# CR78-GU.net
KiCad netlist of a schematic drawn in EAGLE
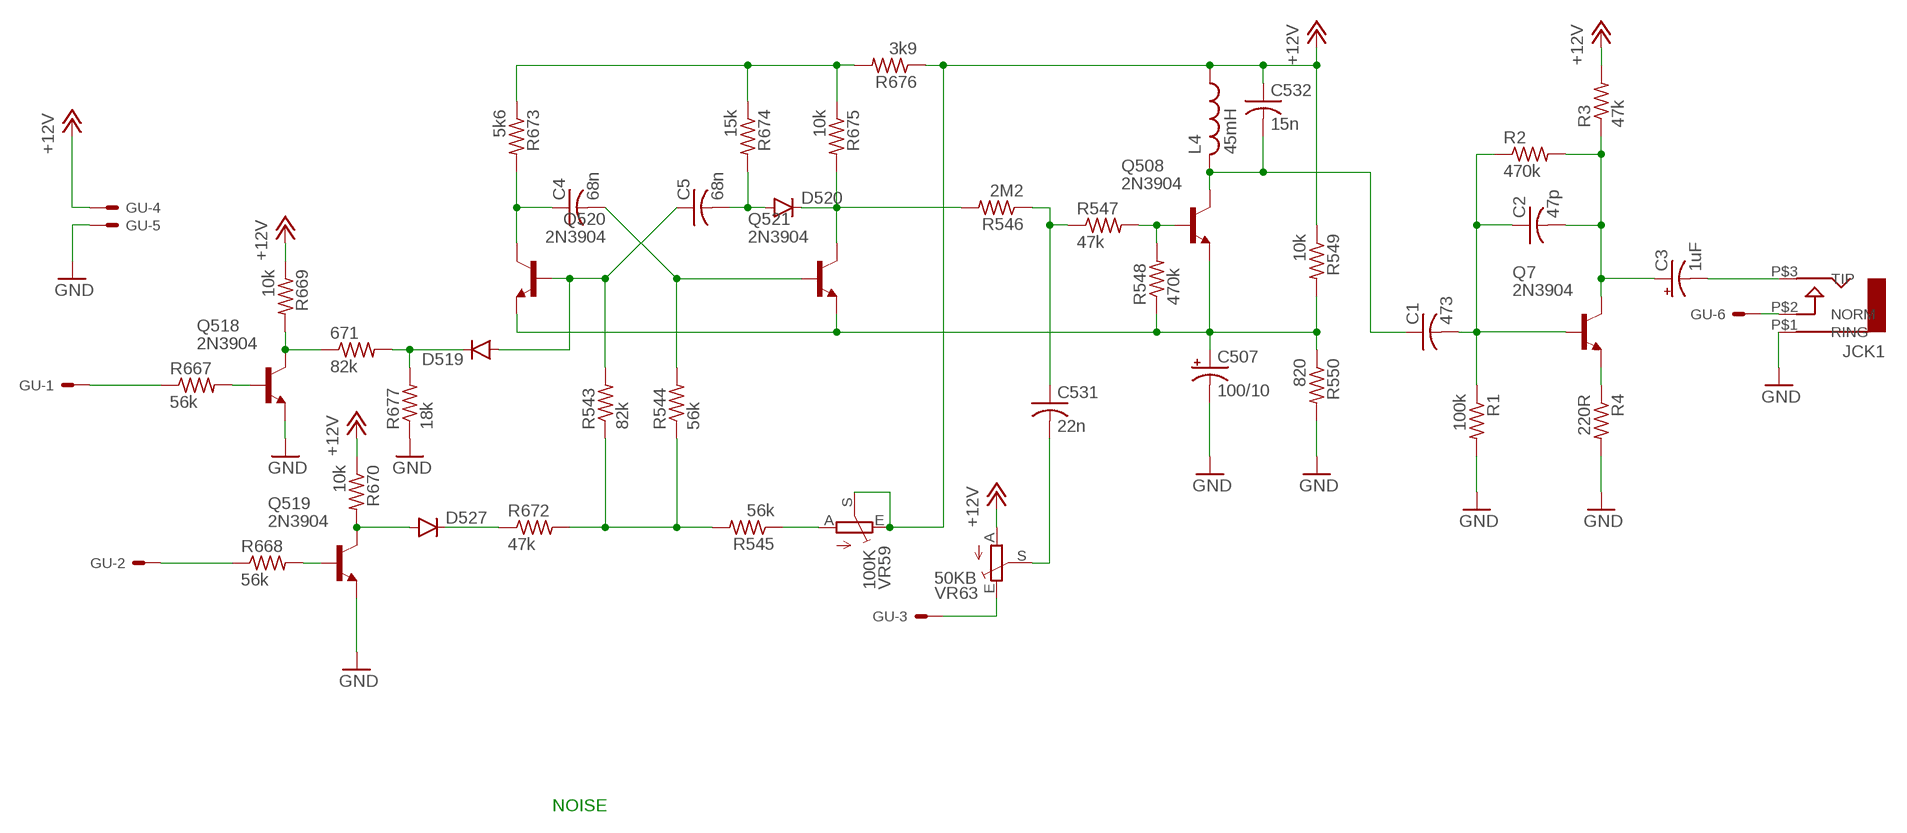
[diagram p0: schematic, sheet 1]

(export (version "E")
  (design (tool "Eeschema 10.0.6"))
  (components
    (comp (ref "671")
      (value "82k")
      (footprint "eagle-import:0207_7")
      (libsource (lib "eagle-import") (part "R-US_0207/7"))
    )
    (comp (ref "C1")
      (value "473")
      (footprint "eagle-import:C050-025X075")
      (libsource (lib "eagle-import") (part "C-US050-025X075"))
    )
    (comp (ref "C2")
      (value "47p")
      (footprint "eagle-import:C050-025X075")
      (libsource (lib "eagle-import") (part "C-US050-025X075"))
    )
    (comp (ref "C3")
      (value "1uF")
      (footprint "eagle-import:B45181A")
      (libsource (lib "eagle-import") (part "CPOL-USB45181A"))
    )
    (comp (ref "C4")
      (value "68n")
      (footprint "eagle-import:C050-025X075")
      (libsource (lib "eagle-import") (part "C-US050-025X075"))
    )
    (comp (ref "C5")
      (value "68n")
      (footprint "eagle-import:C050-025X075")
      (libsource (lib "eagle-import") (part "C-US050-025X075"))
    )
    (comp (ref "C507")
      (value "100/10")
      (footprint "eagle-import:B45181A")
      (libsource (lib "eagle-import") (part "CPOL-USB45181A"))
    )
    (comp (ref "C531")
      (value "22n")
      (footprint "eagle-import:C050-025X075")
      (libsource (lib "eagle-import") (part "C-US050-025X075"))
    )
    (comp (ref "C532")
      (value "15n")
      (footprint "eagle-import:C050-025X075")
      (libsource (lib "eagle-import") (part "C-US050-025X075"))
    )
    (comp (ref "D519")
      (value "DIODE1N4148")
      (footprint "eagle-import:DIODE-1N4148")
      (libsource (lib "eagle-import") (part "DIODE1N4148"))
    )
    (comp (ref "D520")
      (value "DIODE1N4148")
      (footprint "eagle-import:DIODE-1N4148")
      (libsource (lib "eagle-import") (part "DIODE1N4148"))
    )
    (comp (ref "D527")
      (value "DIODE1N4148")
      (footprint "eagle-import:DIODE-1N4148")
      (libsource (lib "eagle-import") (part "DIODE1N4148"))
    )
    (comp (ref "GU")
      (value "22-23-2061")
      (footprint "eagle-import:22-23-2061")
      (fields (field (name "MF") "MOLEX"))
      (libsource (lib "eagle-import") (part "22-23-2061"))
    )
    (comp (ref "JCK1")
      (value "AUDIO-JACK")
      (footprint "eagle-import:ERTHENVAR-JACK-90DEG")
      (libsource (lib "eagle-import") (part "AUDIO-JACK"))
    )
    (comp (ref "L4")
      (value "45mH")
      (footprint "eagle-import:0204_7")
      (libsource (lib "eagle-import") (part "L-US0204/7"))
    )
    (comp (ref "Q7")
      (value "2N3904")
      (footprint "eagle-import:TO92")
      (libsource (lib "eagle-import") (part "2N3904"))
    )
    (comp (ref "Q508")
      (value "2N3904")
      (footprint "eagle-import:TO92")
      (libsource (lib "eagle-import") (part "2N3904"))
    )
    (comp (ref "Q518")
      (value "2N3904")
      (footprint "eagle-import:TO92")
      (libsource (lib "eagle-import") (part "2N3904"))
    )
    (comp (ref "Q519")
      (value "2N3904")
      (footprint "eagle-import:TO92")
      (libsource (lib "eagle-import") (part "2N3904"))
    )
    (comp (ref "Q520")
      (value "2N3904")
      (footprint "eagle-import:TO92")
      (libsource (lib "eagle-import") (part "2N3904"))
    )
    (comp (ref "Q521")
      (value "2N3904")
      (footprint "eagle-import:TO92")
      (libsource (lib "eagle-import") (part "2N3904"))
    )
    (comp (ref "R1")
      (value "100k")
      (footprint "eagle-import:0207_7")
      (libsource (lib "eagle-import") (part "R-US_0207/7"))
    )
    (comp (ref "R2")
      (value "470k")
      (footprint "eagle-import:0207_7")
      (libsource (lib "eagle-import") (part "R-US_0207/7"))
    )
    (comp (ref "R3")
      (value "47k")
      (footprint "eagle-import:0207_7")
      (libsource (lib "eagle-import") (part "R-US_0207/7"))
    )
    (comp (ref "R4")
      (value "220R")
      (footprint "eagle-import:0207_7")
      (libsource (lib "eagle-import") (part "R-US_0207/7"))
    )
    (comp (ref "R543")
      (value "82k")
      (footprint "eagle-import:0207_7")
      (libsource (lib "eagle-import") (part "R-US_0207/7"))
    )
    (comp (ref "R544")
      (value "56k")
      (footprint "eagle-import:0207_7")
      (libsource (lib "eagle-import") (part "R-US_0207/7"))
    )
    (comp (ref "R545")
      (value "56k")
      (footprint "eagle-import:0207_7")
      (libsource (lib "eagle-import") (part "R-US_0207/7"))
    )
    (comp (ref "R546")
      (value "2M2")
      (footprint "eagle-import:0207_7")
      (libsource (lib "eagle-import") (part "R-US_0207/7"))
    )
    (comp (ref "R547")
      (value "47k")
      (footprint "eagle-import:0207_7")
      (libsource (lib "eagle-import") (part "R-US_0207/7"))
    )
    (comp (ref "R548")
      (value "470k")
      (footprint "eagle-import:0207_7")
      (libsource (lib "eagle-import") (part "R-US_0207/7"))
    )
    (comp (ref "R549")
      (value "10k")
      (footprint "eagle-import:0207_7")
      (libsource (lib "eagle-import") (part "R-US_0207/7"))
    )
    (comp (ref "R550")
      (value "820")
      (footprint "eagle-import:0207_7")
      (libsource (lib "eagle-import") (part "R-US_0207/7"))
    )
    (comp (ref "R667")
      (value "56k")
      (footprint "eagle-import:0207_7")
      (libsource (lib "eagle-import") (part "R-US_0207/7"))
    )
    (comp (ref "R668")
      (value "56k")
      (footprint "eagle-import:0207_7")
      (libsource (lib "eagle-import") (part "R-US_0207/7"))
    )
    (comp (ref "R669")
      (value "10k")
      (footprint "eagle-import:0207_7")
      (libsource (lib "eagle-import") (part "R-US_0207/7"))
    )
    (comp (ref "R670")
      (value "10k")
      (footprint "eagle-import:0207_7")
      (libsource (lib "eagle-import") (part "R-US_0207/7"))
    )
    (comp (ref "R672")
      (value "47k")
      (footprint "eagle-import:0207_7")
      (libsource (lib "eagle-import") (part "R-US_0207/7"))
    )
    (comp (ref "R673")
      (value "5k6")
      (footprint "eagle-import:0207_7")
      (libsource (lib "eagle-import") (part "R-US_0207/7"))
    )
    (comp (ref "R674")
      (value "15k")
      (footprint "eagle-import:0207_7")
      (libsource (lib "eagle-import") (part "R-US_0207/7"))
    )
    (comp (ref "R675")
      (value "10k")
      (footprint "eagle-import:0207_7")
      (libsource (lib "eagle-import") (part "R-US_0207/7"))
    )
    (comp (ref "R676")
      (value "3k9")
      (footprint "eagle-import:0207_7")
      (libsource (lib "eagle-import") (part "R-US_0207/7"))
    )
    (comp (ref "R677")
      (value "18k")
      (footprint "eagle-import:0207_7")
      (libsource (lib "eagle-import") (part "R-US_0207/7"))
    )
    (comp (ref "VR59")
      (value "100K")
      (footprint "eagle-import:B64Y")
      (libsource (lib "eagle-import") (part "TRIM_EU-B64Y"))
    )
    (comp (ref "VR63")
      (value "50KB")
      (footprint "eagle-import:B64Y")
      (libsource (lib "eagle-import") (part "TRIM_EU-B64Y"))
    )
  )
  (nets
    (net (code "1") (name "+12V") (class "Default")
      (node (ref "C532") (pin "1") (pinfunction "1_1") (pintype "passive"))
      (node (ref "GU") (pin "4") (pinfunction "S_4") (pintype "passive"))
      (node (ref "L4") (pin "1") (pinfunction "1_1") (pintype "passive"))
      (node (ref "R3") (pin "2") (pinfunction "2_2") (pintype "passive"))
      (node (ref "R549") (pin "1") (pinfunction "1_1") (pintype "passive"))
      (node (ref "R669") (pin "1") (pinfunction "1_1") (pintype "passive"))
      (node (ref "R670") (pin "1") (pinfunction "1_1") (pintype "passive"))
      (node (ref "R676") (pin "1") (pinfunction "1_1") (pintype "passive"))
      (node (ref "VR59") (pin "E") (pinfunction "E_E") (pintype "passive"))
      (node (ref "VR59") (pin "S") (pinfunction "S_S") (pintype "passive"))
      (node (ref "VR63") (pin "A") (pinfunction "A_A") (pintype "passive"))
    )
    (net (code "2") (name "GND") (class "Default")
      (node (ref "C507") (pin "-") (pinfunction "-_-") (pintype "passive"))
      (node (ref "GU") (pin "5") (pinfunction "S_5") (pintype "passive"))
      (node (ref "JCK1") (pin "P$1") (pinfunction "RING_P$1") (pintype "bidirectional"))
      (node (ref "Q518") (pin "3") (pinfunction "E_3") (pintype "passive"))
      (node (ref "Q519") (pin "3") (pinfunction "E_3") (pintype "passive"))
      (node (ref "R1") (pin "2") (pinfunction "2_2") (pintype "passive"))
      (node (ref "R4") (pin "2") (pinfunction "2_2") (pintype "passive"))
      (node (ref "R550") (pin "2") (pinfunction "2_2") (pintype "passive"))
      (node (ref "R677") (pin "1") (pinfunction "1_1") (pintype "passive"))
    )
    (net (code "3") (name "Net-(671-Pad2)") (class "Default")
      (node (ref "671") (pin "2") (pinfunction "2_2") (pintype "passive"))
      (node (ref "D519") (pin "C") (pinfunction "C_C") (pintype "passive"))
      (node (ref "R677") (pin "2") (pinfunction "2_2") (pintype "passive"))
    )
    (net (code "4") (name "Net-(C5-Pad2)") (class "Default")
      (node (ref "C5") (pin "2") (pinfunction "2_2") (pintype "passive"))
      (node (ref "D520") (pin "A") (pinfunction "A_A") (pintype "passive"))
      (node (ref "R674") (pin "2") (pinfunction "2_2") (pintype "passive"))
    )
    (net (code "5") (name "Net-(C531-Pad1)") (class "Default")
      (node (ref "C531") (pin "1") (pinfunction "1_1") (pintype "passive"))
      (node (ref "R546") (pin "1") (pinfunction "1_1") (pintype "passive"))
      (node (ref "R547") (pin "1") (pinfunction "1_1") (pintype "passive"))
    )
    (net (code "6") (name "Net-(C531-Pad2)") (class "Default")
      (node (ref "C531") (pin "2") (pinfunction "2_2") (pintype "passive"))
      (node (ref "VR63") (pin "S") (pinfunction "S_S") (pintype "passive"))
    )
    (net (code "7") (name "Net-(D527-PadC)") (class "Default")
      (node (ref "D527") (pin "C") (pinfunction "C_C") (pintype "passive"))
      (node (ref "R672") (pin "1") (pinfunction "1_1") (pintype "passive"))
    )
    (net (code "8") (name "Net-(GUA-S)") (class "Default")
      (node (ref "GU") (pin "1") (pinfunction "S_1") (pintype "passive"))
      (node (ref "R667") (pin "1") (pinfunction "1_1") (pintype "passive"))
    )
    (net (code "9") (name "Net-(GUB-S)") (class "Default")
      (node (ref "GU") (pin "2") (pinfunction "S_2") (pintype "passive"))
      (node (ref "R668") (pin "1") (pinfunction "1_1") (pintype "passive"))
    )
    (net (code "10") (name "Net-(GUC-S)") (class "Default")
      (node (ref "GU") (pin "3") (pinfunction "S_3") (pintype "passive"))
      (node (ref "VR63") (pin "E") (pinfunction "E_E") (pintype "passive"))
    )
    (net (code "11") (name "Net-(GUF-S)") (class "Default")
      (node (ref "GU") (pin "6") (pinfunction "S_6") (pintype "passive"))
      (node (ref "JCK1") (pin "P$2") (pinfunction "NORM_P$2") (pintype "bidirectional"))
    )
    (net (code "12") (name "Net-(JCK1-TIP)") (class "Default")
      (node (ref "C3") (pin "-") (pinfunction "-_-") (pintype "passive"))
      (node (ref "JCK1") (pin "P$3") (pinfunction "TIP_P$3") (pintype "bidirectional"))
    )
    (net (code "13") (name "Net-(Q7-B)") (class "Default")
      (node (ref "C1") (pin "2") (pinfunction "2_2") (pintype "passive"))
      (node (ref "C2") (pin "1") (pinfunction "1_1") (pintype "passive"))
      (node (ref "Q7") (pin "2") (pinfunction "B_2") (pintype "passive"))
      (node (ref "R1") (pin "1") (pinfunction "1_1") (pintype "passive"))
      (node (ref "R2") (pin "1") (pinfunction "1_1") (pintype "passive"))
    )
    (net (code "14") (name "Net-(Q7-C)") (class "Default")
      (node (ref "C2") (pin "2") (pinfunction "2_2") (pintype "passive"))
      (node (ref "C3") (pin "+") (pinfunction "+_+") (pintype "passive"))
      (node (ref "Q7") (pin "1") (pinfunction "C_1") (pintype "passive"))
      (node (ref "R2") (pin "2") (pinfunction "2_2") (pintype "passive"))
      (node (ref "R3") (pin "1") (pinfunction "1_1") (pintype "passive"))
    )
    (net (code "15") (name "Net-(Q7-E)") (class "Default")
      (node (ref "Q7") (pin "3") (pinfunction "E_3") (pintype "passive"))
      (node (ref "R4") (pin "1") (pinfunction "1_1") (pintype "passive"))
    )
    (net (code "16") (name "Net-(Q508-B)") (class "Default")
      (node (ref "Q508") (pin "2") (pinfunction "B_2") (pintype "passive"))
      (node (ref "R547") (pin "2") (pinfunction "2_2") (pintype "passive"))
      (node (ref "R548") (pin "2") (pinfunction "2_2") (pintype "passive"))
    )
    (net (code "17") (name "Net-(Q508-C)") (class "Default")
      (node (ref "C1") (pin "1") (pinfunction "1_1") (pintype "passive"))
      (node (ref "C532") (pin "2") (pinfunction "2_2") (pintype "passive"))
      (node (ref "L4") (pin "2") (pinfunction "2_2") (pintype "passive"))
      (node (ref "Q508") (pin "1") (pinfunction "C_1") (pintype "passive"))
    )
    (net (code "18") (name "Net-(Q508-E)") (class "Default")
      (node (ref "C507") (pin "+") (pinfunction "+_+") (pintype "passive"))
      (node (ref "Q508") (pin "3") (pinfunction "E_3") (pintype "passive"))
      (node (ref "Q520") (pin "3") (pinfunction "E_3") (pintype "passive"))
      (node (ref "Q521") (pin "3") (pinfunction "E_3") (pintype "passive"))
      (node (ref "R548") (pin "1") (pinfunction "1_1") (pintype "passive"))
      (node (ref "R549") (pin "2") (pinfunction "2_2") (pintype "passive"))
      (node (ref "R550") (pin "1") (pinfunction "1_1") (pintype "passive"))
    )
    (net (code "19") (name "Net-(Q518-B)") (class "Default")
      (node (ref "Q518") (pin "2") (pinfunction "B_2") (pintype "passive"))
      (node (ref "R667") (pin "2") (pinfunction "2_2") (pintype "passive"))
    )
    (net (code "20") (name "Net-(Q518-C)") (class "Default")
      (node (ref "671") (pin "1") (pinfunction "1_1") (pintype "passive"))
      (node (ref "Q518") (pin "1") (pinfunction "C_1") (pintype "passive"))
      (node (ref "R669") (pin "2") (pinfunction "2_2") (pintype "passive"))
    )
    (net (code "21") (name "Net-(Q519-B)") (class "Default")
      (node (ref "Q519") (pin "2") (pinfunction "B_2") (pintype "passive"))
      (node (ref "R668") (pin "2") (pinfunction "2_2") (pintype "passive"))
    )
    (net (code "22") (name "Net-(Q519-C)") (class "Default")
      (node (ref "D527") (pin "A") (pinfunction "A_A") (pintype "passive"))
      (node (ref "Q519") (pin "1") (pinfunction "C_1") (pintype "passive"))
      (node (ref "R670") (pin "2") (pinfunction "2_2") (pintype "passive"))
    )
    (net (code "23") (name "Net-(Q520-B)") (class "Default")
      (node (ref "C5") (pin "1") (pinfunction "1_1") (pintype "passive"))
      (node (ref "D519") (pin "A") (pinfunction "A_A") (pintype "passive"))
      (node (ref "Q520") (pin "2") (pinfunction "B_2") (pintype "passive"))
      (node (ref "R543") (pin "2") (pinfunction "2_2") (pintype "passive"))
    )
    (net (code "24") (name "Net-(Q520-C)") (class "Default")
      (node (ref "C4") (pin "1") (pinfunction "1_1") (pintype "passive"))
      (node (ref "Q520") (pin "1") (pinfunction "C_1") (pintype "passive"))
      (node (ref "R673") (pin "2") (pinfunction "2_2") (pintype "passive"))
    )
    (net (code "25") (name "Net-(Q521-B)") (class "Default")
      (node (ref "C4") (pin "2") (pinfunction "2_2") (pintype "passive"))
      (node (ref "Q521") (pin "2") (pinfunction "B_2") (pintype "passive"))
      (node (ref "R544") (pin "2") (pinfunction "2_2") (pintype "passive"))
    )
    (net (code "26") (name "Net-(Q521-C)") (class "Default")
      (node (ref "D520") (pin "C") (pinfunction "C_C") (pintype "passive"))
      (node (ref "Q521") (pin "1") (pinfunction "C_1") (pintype "passive"))
      (node (ref "R546") (pin "2") (pinfunction "2_2") (pintype "passive"))
      (node (ref "R675") (pin "2") (pinfunction "2_2") (pintype "passive"))
    )
    (net (code "27") (name "Net-(R543-Pad1)") (class "Default")
      (node (ref "R543") (pin "1") (pinfunction "1_1") (pintype "passive"))
      (node (ref "R544") (pin "1") (pinfunction "1_1") (pintype "passive"))
      (node (ref "R545") (pin "2") (pinfunction "2_2") (pintype "passive"))
      (node (ref "R672") (pin "2") (pinfunction "2_2") (pintype "passive"))
    )
    (net (code "28") (name "Net-(R545-Pad1)") (class "Default")
      (node (ref "R545") (pin "1") (pinfunction "1_1") (pintype "passive"))
      (node (ref "VR59") (pin "A") (pinfunction "A_A") (pintype "passive"))
    )
    (net (code "29") (name "Net-(R673-Pad1)") (class "Default")
      (node (ref "R673") (pin "1") (pinfunction "1_1") (pintype "passive"))
      (node (ref "R674") (pin "1") (pinfunction "1_1") (pintype "passive"))
      (node (ref "R675") (pin "1") (pinfunction "1_1") (pintype "passive"))
      (node (ref "R676") (pin "2") (pinfunction "2_2") (pintype "passive"))
    )
  )
)
